# Power.net
KiCad netlist of a schematic drawn in Altium Designer
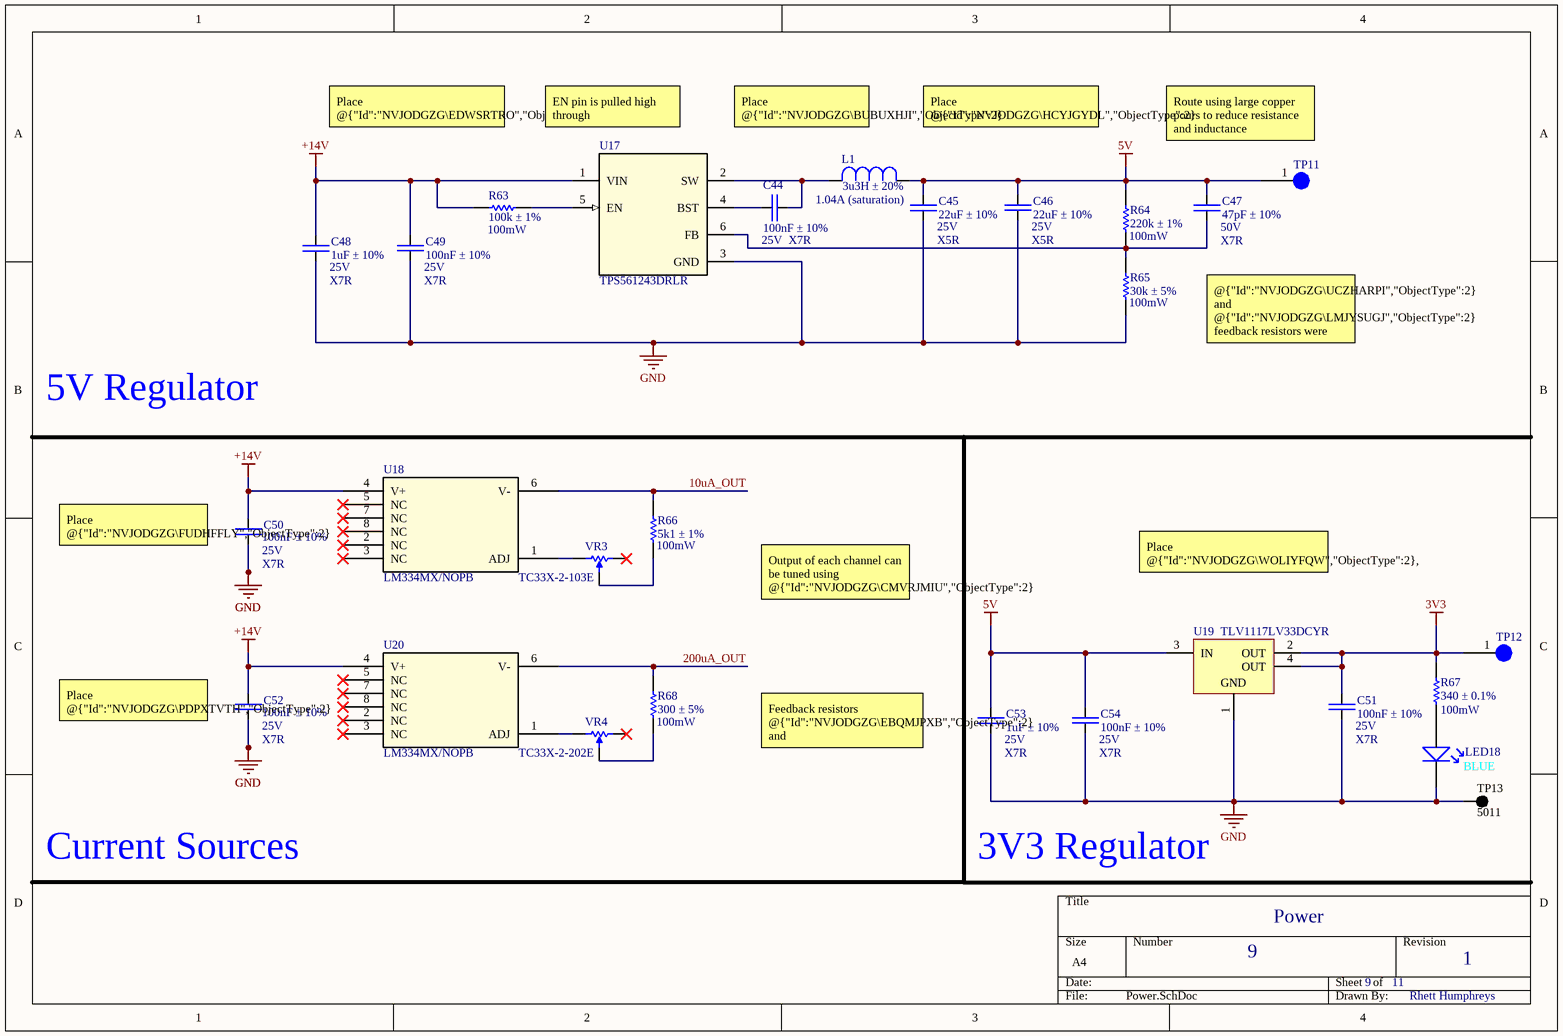
[diagram p0: Power.SchDoc]

(export (version "E")
  (design (tool "Eeschema 10.0.6"))
  (components
    (comp (ref "C44")
      (value "100nF ± 10%")
      (footprint "CAP-0603")
      (description "Capacitor chip unpolarized. 0603")
      (libsource (lib "Master") (part "CAP-0603"))
    )
    (comp (ref "C45")
      (value "22uF ± 10%")
      (footprint "CAP-1206")
      (description "Capacitor chip unpolarized. 0603")
      (libsource (lib "Master") (part "CAP-1206"))
    )
    (comp (ref "C46")
      (value "22uF ± 10%")
      (footprint "CAP-1206")
      (description "Capacitor chip unpolarized. 0603")
      (libsource (lib "Master") (part "CAP-1206"))
    )
    (comp (ref "C47")
      (value "47pF ± 10%")
      (footprint "CAP-0603")
      (description "Capacitor chip unpolarized. 0603")
      (libsource (lib "Master") (part "CAP-0603"))
    )
    (comp (ref "C48")
      (value "1uF ± 10%")
      (footprint "CAP-0805")
      (description "Capacitor chip unpolarized. 0603")
      (libsource (lib "Master") (part "CAP-0805"))
    )
    (comp (ref "C49")
      (value "100nF ± 10%")
      (footprint "CAP-0603")
      (description "Capacitor chip unpolarized. 0603")
      (libsource (lib "Master") (part "CAP-0603"))
    )
    (comp (ref "C50")
      (value "100nF ± 10%")
      (footprint "CAP-0603")
      (description "Capacitor chip unpolarized. 0603")
      (libsource (lib "Master") (part "CAP-0603"))
    )
    (comp (ref "C51")
      (value "100nF ± 10%")
      (footprint "CAP-0603")
      (description "Capacitor chip unpolarized. 0603")
      (libsource (lib "Master") (part "CAP-0603"))
    )
    (comp (ref "C52")
      (value "100nF ± 10%")
      (footprint "CAP-0603")
      (description "Capacitor chip unpolarized. 0603")
      (libsource (lib "Master") (part "CAP-0603"))
    )
    (comp (ref "C53")
      (value "1uF ± 10%")
      (footprint "CAP-0805")
      (description "Capacitor chip unpolarized. 0603")
      (libsource (lib "Master") (part "CAP-0805"))
    )
    (comp (ref "C54")
      (value "100nF ± 10%")
      (footprint "CAP-0603")
      (description "Capacitor chip unpolarized. 0603")
      (libsource (lib "Master") (part "CAP-0603"))
    )
    (comp (ref "L1")
      (value "3u3H ± 20%")
      (footprint "IND_TAIYO_CBC3225_TAY")
      (description "No Description Available")
      (libsource (lib "Master") (part "CBC3225T3R3MR"))
    )
    (comp (ref "LED18") (value "~") (footprint "0603 LED") (libsource (lib "Master") (part "0603 LED")))
    (comp (ref "R63")
      (value "100k ± 1%")
      (footprint "RES-0603")
      (description "Resistor chip. 0603")
      (libsource (lib "Master") (part "RES-0603"))
    )
    (comp (ref "R64")
      (value "220k ± 1%")
      (footprint "RES-0603")
      (description "Resistor chip. 0603")
      (libsource (lib "Master") (part "RES-0603"))
    )
    (comp (ref "R65")
      (value "30k ± 5%")
      (footprint "RES-0603")
      (description "Resistor chip. 0603")
      (libsource (lib "Master") (part "RES-0603"))
    )
    (comp (ref "R66")
      (value "5k1 ± 1%")
      (footprint "RES-0603")
      (description "Resistor chip. 0603")
      (libsource (lib "Master") (part "RES-0603"))
    )
    (comp (ref "R67")
      (value "340 ± 0.1%")
      (footprint "RES-0603")
      (description "Resistor chip. 0603")
      (libsource (lib "Master") (part "RES-0603"))
    )
    (comp (ref "R68")
      (value "300 ± 5%")
      (footprint "RES-0603")
      (description "Resistor chip. 0603")
      (libsource (lib "Master") (part "RES-0603"))
    )
    (comp (ref "TP11")
      (value "Test-Point 3mm")
      (footprint "TestPoint 3mm")
      (libsource (lib "Master") (part "Test-Point 3mm"))
    )
    (comp (ref "TP12")
      (value "Test-Point 3mm")
      (footprint "TestPoint 3mm")
      (libsource (lib "Master") (part "Test-Point 3mm"))
    )
    (comp (ref "TP13")
      (value "5011")
      (footprint "KSTN-5011_V")
      (description "Test Point, Black, Through Hole, RoHS, Bulk")
      (fields (field (name "MANUFACTURER") "Keystone"))
      (libsource (lib "Altium Content Vault") (part "TESTPOINT_BLACK"))
    )
    (comp (ref "U17")
      (value "TPS561243DRLR")
      (footprint "DRL0006A-MFG")
      (description "No Description Available")
      (libsource (lib "Master") (part "TPS561243DRLR"))
    )
    (comp (ref "U18")
      (value "LM334MX/NOPB")
      (footprint "SO-8_STM")
      (description "No Description Available")
      (libsource (lib "Master") (part "LM234DT"))
    )
    (comp (ref "U19")
      (value "TLV1117LV33DCYR")
      (footprint "DCY0004A_N")
      (fields (field (name "MANUFACTURER") "Texas Instruments"))
      (libsource (lib "Altium Content Vault") (part "TI-TLV1117LV33DCY4"))
    )
    (comp (ref "U20")
      (value "LM334MX/NOPB")
      (footprint "SO-8_STM")
      (description "No Description Available")
      (libsource (lib "Master") (part "LM234DT"))
    )
    (comp (ref "VR3")
      (value "TC33X-2-103E")
      (footprint "BOUR-TC33X-2_V")
      (description "Trimming Potentiometer, 2000 Ohm, -40 to 100 degC, 3-Pin SMD, RoHS, Tape and Reel")
      (fields (field (name "TOLERANCE") "25%") (field (name "MANUFACTURER") "Bourns"))
      (libsource (lib "Altium Content Vault") (part "RES-ADJ-3_A"))
    )
    (comp (ref "VR4")
      (value "TC33X-2-202E")
      (footprint "BOUR-TC33X-2_V")
      (description "Trimming Potentiometer, 2000 Ohm, -40 to 100 degC, 3-Pin SMD, RoHS, Tape and Reel")
      (fields (field (name "TOLERANCE") "25%") (field (name "MANUFACTURER") "Bourns"))
      (libsource (lib "Altium Content Vault") (part "RES-ADJ-3_A"))
    )
  )
  (nets
    (net (code "1") (name "+14V") (class "Default")
      (node (ref "C48") (pin "2") (pintype "passive"))
      (node (ref "C49") (pin "2") (pintype "passive"))
      (node (ref "C50") (pin "2") (pintype "passive"))
      (node (ref "C52") (pin "2") (pintype "passive"))
      (node (ref "R63") (pin "1") (pintype "passive"))
      (node (ref "U17") (pin "1") (pinfunction "VIN_1") (pintype "power_in"))
      (node (ref "U18") (pin "4") (pinfunction "V+_4") (pintype "power_in"))
      (node (ref "U20") (pin "4") (pinfunction "V+_4") (pintype "power_in"))
    )
    (net (code "2") (name "/10uA_OUT") (class "Default")
      (node (ref "R66") (pin "1") (pintype "passive"))
      (node (ref "U18") (pin "6") (pinfunction "V-_6") (pintype "power_in"))
    )
    (net (code "3") (name "/200uA_OUT") (class "Default")
      (node (ref "R68") (pin "1") (pintype "passive"))
      (node (ref "U20") (pin "6") (pinfunction "V-_6") (pintype "power_in"))
    )
    (net (code "4") (name "3V3") (class "Default")
      (node (ref "C51") (pin "2") (pintype "passive"))
      (node (ref "R67") (pin "1") (pintype "passive"))
      (node (ref "TP12") (pin "1") (pintype "passive"))
      (node (ref "U19") (pin "2") (pinfunction "OUT_2") (pintype "power_in"))
      (node (ref "U19") (pin "4") (pinfunction "OUT_4") (pintype "power_in"))
    )
    (net (code "5") (name "5V") (class "Default")
      (node (ref "C45") (pin "2") (pintype "passive"))
      (node (ref "C46") (pin "2") (pintype "passive"))
      (node (ref "C47") (pin "2") (pintype "passive"))
      (node (ref "C53") (pin "2") (pintype "passive"))
      (node (ref "C54") (pin "2") (pintype "passive"))
      (node (ref "L1") (pin "1") (pinfunction "1_1") (pintype "passive"))
      (node (ref "R64") (pin "1") (pintype "passive"))
      (node (ref "TP11") (pin "1") (pintype "passive"))
      (node (ref "U19") (pin "3") (pinfunction "IN_3") (pintype "power_in"))
    )
    (net (code "6") (name "GND") (class "Default")
      (node (ref "C45") (pin "1") (pintype "passive"))
      (node (ref "C46") (pin "1") (pintype "passive"))
      (node (ref "C48") (pin "1") (pintype "passive"))
      (node (ref "C49") (pin "1") (pintype "passive"))
      (node (ref "C50") (pin "1") (pintype "passive"))
      (node (ref "C51") (pin "1") (pintype "passive"))
      (node (ref "C52") (pin "1") (pintype "passive"))
      (node (ref "C53") (pin "1") (pintype "passive"))
      (node (ref "C54") (pin "1") (pintype "passive"))
      (node (ref "LED18") (pin "2") (pinfunction "5_2") (pintype "passive"))
      (node (ref "R65") (pin "2") (pintype "passive"))
      (node (ref "TP13") (pin "1") (pinfunction "1_1") (pintype "passive"))
      (node (ref "U17") (pin "3") (pinfunction "GND_3") (pintype "power_in"))
      (node (ref "U19") (pin "1") (pinfunction "GND_1") (pintype "power_in"))
    )
    (net (code "7") (name "Net-(LED18-6)") (class "Default")
      (node (ref "LED18") (pin "1") (pinfunction "6_1") (pintype "passive"))
      (node (ref "R67") (pin "2") (pintype "passive"))
    )
    (net (code "8") (name "Net-(R66-Pad2)") (class "Default")
      (node (ref "R66") (pin "2") (pintype "passive"))
      (node (ref "VR3") (pin "2") (pinfunction "2_2") (pintype "passive"))
    )
    (net (code "9") (name "Net-(R68-Pad2)") (class "Default")
      (node (ref "R68") (pin "2") (pintype "passive"))
      (node (ref "VR4") (pin "2") (pinfunction "2_2") (pintype "passive"))
    )
    (net (code "10") (name "Net-(U17-BST)") (class "Default")
      (node (ref "C44") (pin "1") (pintype "passive"))
      (node (ref "U17") (pin "4") (pinfunction "BST_4") (pintype "passive"))
    )
    (net (code "11") (name "Net-(U17-EN)") (class "Default")
      (node (ref "R63") (pin "2") (pintype "passive"))
      (node (ref "U17") (pin "5") (pinfunction "EN_5") (pintype "input"))
    )
    (net (code "12") (name "Net-(U17-FB)") (class "Default")
      (node (ref "C47") (pin "1") (pintype "passive"))
      (node (ref "R64") (pin "2") (pintype "passive"))
      (node (ref "R65") (pin "1") (pintype "passive"))
      (node (ref "U17") (pin "6") (pinfunction "FB_6") (pintype "passive"))
    )
    (net (code "13") (name "Net-(U17-SW)") (class "Default")
      (node (ref "C44") (pin "2") (pintype "passive"))
      (node (ref "L1") (pin "2") (pinfunction "2_2") (pintype "passive"))
      (node (ref "U17") (pin "2") (pinfunction "SW_2") (pintype "passive"))
    )
    (net (code "14") (name "Net-(U18-ADJ)") (class "Default")
      (node (ref "U18") (pin "1") (pinfunction "ADJ_1") (pintype "passive"))
      (node (ref "VR3") (pin "1") (pinfunction "1_1") (pintype "passive"))
    )
    (net (code "15") (name "Net-(U20-ADJ)") (class "Default")
      (node (ref "U20") (pin "1") (pinfunction "ADJ_1") (pintype "passive"))
      (node (ref "VR4") (pin "1") (pinfunction "1_1") (pintype "passive"))
    )
    (net (code "16") (name "unconnected-(U18-NC-Pad2)") (class "Default")
      (node (ref "U18") (pin "2") (pinfunction "NC_2") (pintype "passive+no_connect"))
    )
    (net (code "17") (name "unconnected-(U18-NC-Pad3)") (class "Default")
      (node (ref "U18") (pin "3") (pinfunction "NC_3") (pintype "passive+no_connect"))
    )
    (net (code "18") (name "unconnected-(U18-NC-Pad5)") (class "Default")
      (node (ref "U18") (pin "5") (pinfunction "NC_5") (pintype "passive+no_connect"))
    )
    (net (code "19") (name "unconnected-(U18-NC-Pad7)") (class "Default")
      (node (ref "U18") (pin "7") (pinfunction "NC_7") (pintype "passive+no_connect"))
    )
    (net (code "20") (name "unconnected-(U18-NC-Pad8)") (class "Default")
      (node (ref "U18") (pin "8") (pinfunction "NC_8") (pintype "passive+no_connect"))
    )
    (net (code "21") (name "unconnected-(U20-NC-Pad2)") (class "Default")
      (node (ref "U20") (pin "2") (pinfunction "NC_2") (pintype "passive+no_connect"))
    )
    (net (code "22") (name "unconnected-(U20-NC-Pad3)") (class "Default")
      (node (ref "U20") (pin "3") (pinfunction "NC_3") (pintype "passive+no_connect"))
    )
    (net (code "23") (name "unconnected-(U20-NC-Pad5)") (class "Default")
      (node (ref "U20") (pin "5") (pinfunction "NC_5") (pintype "passive+no_connect"))
    )
    (net (code "24") (name "unconnected-(U20-NC-Pad7)") (class "Default")
      (node (ref "U20") (pin "7") (pinfunction "NC_7") (pintype "passive+no_connect"))
    )
    (net (code "25") (name "unconnected-(U20-NC-Pad8)") (class "Default")
      (node (ref "U20") (pin "8") (pinfunction "NC_8") (pintype "passive+no_connect"))
    )
    (net (code "26") (name "unconnected-(VR3-Pad3)") (class "Default")
      (node (ref "VR3") (pin "3") (pinfunction "3_3") (pintype "passive+no_connect"))
    )
    (net (code "27") (name "unconnected-(VR4-Pad3)") (class "Default")
      (node (ref "VR4") (pin "3") (pinfunction "3_3") (pintype "passive+no_connect"))
    )
  )
)
